# Poti.net
KiCad netlist of a schematic drawn in EAGLE
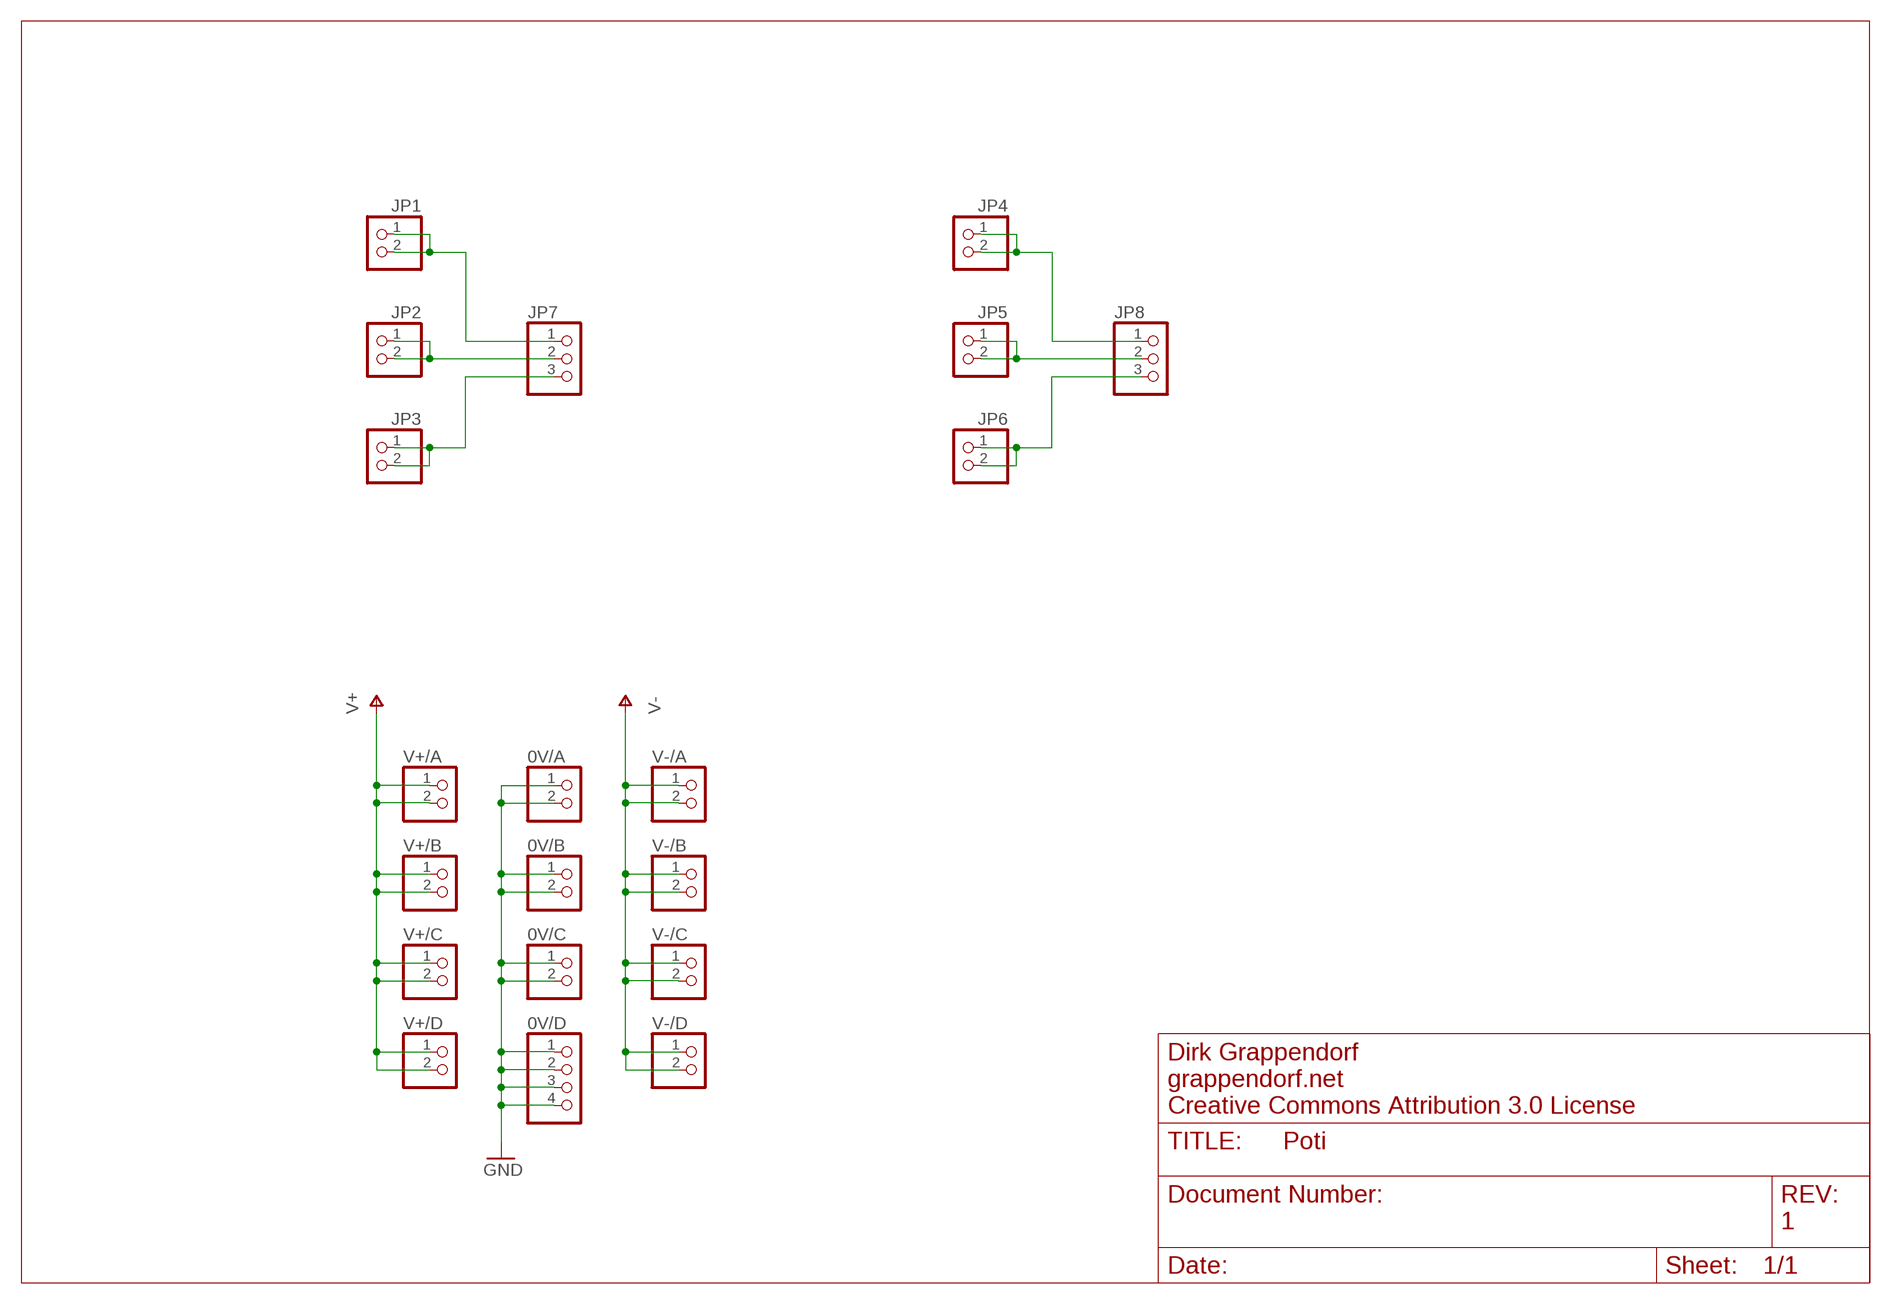
[diagram p0: schematic, sheet 1]

(export (version "E")
  (design (tool "Eeschema 10.0.6"))
  (components
    (comp (ref "0V/A")
      (value "PINHD-1X2")
      (footprint "eagle-import:1X02")
      (libsource (lib "eagle-import") (part "PINHD-1X2"))
    )
    (comp (ref "0V/B")
      (value "PINHD-1X2")
      (footprint "eagle-import:1X02")
      (libsource (lib "eagle-import") (part "PINHD-1X2"))
    )
    (comp (ref "0V/C")
      (value "PINHD-1X2")
      (footprint "eagle-import:1X02")
      (libsource (lib "eagle-import") (part "PINHD-1X2"))
    )
    (comp (ref "0V/D")
      (value "PINHD-1X4")
      (footprint "eagle-import:1X04")
      (libsource (lib "eagle-import") (part "PINHD-1X4"))
    )
    (comp (ref "JP1")
      (value "PINHD-1X2")
      (footprint "eagle-import:1X02")
      (libsource (lib "eagle-import") (part "PINHD-1X2"))
    )
    (comp (ref "JP2")
      (value "PINHD-1X2")
      (footprint "eagle-import:1X02")
      (libsource (lib "eagle-import") (part "PINHD-1X2"))
    )
    (comp (ref "JP3")
      (value "PINHD-1X2")
      (footprint "eagle-import:1X02")
      (libsource (lib "eagle-import") (part "PINHD-1X2"))
    )
    (comp (ref "JP4")
      (value "PINHD-1X2")
      (footprint "eagle-import:1X02")
      (libsource (lib "eagle-import") (part "PINHD-1X2"))
    )
    (comp (ref "JP5")
      (value "PINHD-1X2")
      (footprint "eagle-import:1X02")
      (libsource (lib "eagle-import") (part "PINHD-1X2"))
    )
    (comp (ref "JP6")
      (value "PINHD-1X2")
      (footprint "eagle-import:1X02")
      (libsource (lib "eagle-import") (part "PINHD-1X2"))
    )
    (comp (ref "JP7")
      (value "PINHD-1X3")
      (footprint "eagle-import:1X03")
      (libsource (lib "eagle-import") (part "PINHD-1X3"))
    )
    (comp (ref "JP8")
      (value "PINHD-1X3")
      (footprint "eagle-import:1X03")
      (libsource (lib "eagle-import") (part "PINHD-1X3"))
    )
    (comp (ref "V+/A")
      (value "PINHD-1X2")
      (footprint "eagle-import:1X02")
      (libsource (lib "eagle-import") (part "PINHD-1X2"))
    )
    (comp (ref "V+/B")
      (value "PINHD-1X2")
      (footprint "eagle-import:1X02")
      (libsource (lib "eagle-import") (part "PINHD-1X2"))
    )
    (comp (ref "V+/C")
      (value "PINHD-1X2")
      (footprint "eagle-import:1X02")
      (libsource (lib "eagle-import") (part "PINHD-1X2"))
    )
    (comp (ref "V+/D")
      (value "PINHD-1X2")
      (footprint "eagle-import:1X02")
      (libsource (lib "eagle-import") (part "PINHD-1X2"))
    )
    (comp (ref "V-/A")
      (value "PINHD-1X2")
      (footprint "eagle-import:1X02")
      (libsource (lib "eagle-import") (part "PINHD-1X2"))
    )
    (comp (ref "V-/B")
      (value "PINHD-1X2")
      (footprint "eagle-import:1X02")
      (libsource (lib "eagle-import") (part "PINHD-1X2"))
    )
    (comp (ref "V-/C")
      (value "PINHD-1X2")
      (footprint "eagle-import:1X02")
      (libsource (lib "eagle-import") (part "PINHD-1X2"))
    )
    (comp (ref "V-/D")
      (value "PINHD-1X2")
      (footprint "eagle-import:1X02")
      (libsource (lib "eagle-import") (part "PINHD-1X2"))
    )
  )
  (nets
    (net (code "1") (name "GND") (class "Default")
      (node (ref "0V/A") (pin "1") (pinfunction "1_1") (pintype "passive"))
      (node (ref "0V/A") (pin "2") (pinfunction "2_2") (pintype "passive"))
      (node (ref "0V/B") (pin "1") (pinfunction "1_1") (pintype "passive"))
      (node (ref "0V/B") (pin "2") (pinfunction "2_2") (pintype "passive"))
      (node (ref "0V/C") (pin "1") (pinfunction "1_1") (pintype "passive"))
      (node (ref "0V/C") (pin "2") (pinfunction "2_2") (pintype "passive"))
      (node (ref "0V/D") (pin "1") (pinfunction "1_1") (pintype "passive"))
      (node (ref "0V/D") (pin "2") (pinfunction "2_2") (pintype "passive"))
      (node (ref "0V/D") (pin "3") (pinfunction "3_3") (pintype "passive"))
      (node (ref "0V/D") (pin "4") (pinfunction "4_4") (pintype "passive"))
    )
    (net (code "2") (name "Net-(JP1-Pad1)") (class "Default")
      (node (ref "JP1") (pin "1") (pinfunction "1_1") (pintype "passive"))
      (node (ref "JP1") (pin "2") (pinfunction "2_2") (pintype "passive"))
      (node (ref "JP7") (pin "1") (pinfunction "1_1") (pintype "passive"))
    )
    (net (code "3") (name "Net-(JP2-Pad1)") (class "Default")
      (node (ref "JP2") (pin "1") (pinfunction "1_1") (pintype "passive"))
      (node (ref "JP2") (pin "2") (pinfunction "2_2") (pintype "passive"))
      (node (ref "JP7") (pin "2") (pinfunction "2_2") (pintype "passive"))
    )
    (net (code "4") (name "Net-(JP3-Pad1)") (class "Default")
      (node (ref "JP3") (pin "1") (pinfunction "1_1") (pintype "passive"))
      (node (ref "JP3") (pin "2") (pinfunction "2_2") (pintype "passive"))
      (node (ref "JP7") (pin "3") (pinfunction "3_3") (pintype "passive"))
    )
    (net (code "5") (name "Net-(JP4-Pad1)") (class "Default")
      (node (ref "JP4") (pin "1") (pinfunction "1_1") (pintype "passive"))
      (node (ref "JP4") (pin "2") (pinfunction "2_2") (pintype "passive"))
      (node (ref "JP8") (pin "1") (pinfunction "1_1") (pintype "passive"))
    )
    (net (code "6") (name "Net-(JP5-Pad1)") (class "Default")
      (node (ref "JP5") (pin "1") (pinfunction "1_1") (pintype "passive"))
      (node (ref "JP5") (pin "2") (pinfunction "2_2") (pintype "passive"))
      (node (ref "JP8") (pin "2") (pinfunction "2_2") (pintype "passive"))
    )
    (net (code "7") (name "Net-(JP6-Pad1)") (class "Default")
      (node (ref "JP6") (pin "1") (pinfunction "1_1") (pintype "passive"))
      (node (ref "JP6") (pin "2") (pinfunction "2_2") (pintype "passive"))
      (node (ref "JP8") (pin "3") (pinfunction "3_3") (pintype "passive"))
    )
    (net (code "8") (name "V+") (class "Default")
      (node (ref "V+/A") (pin "1") (pinfunction "1_1") (pintype "passive"))
      (node (ref "V+/A") (pin "2") (pinfunction "2_2") (pintype "passive"))
      (node (ref "V+/B") (pin "1") (pinfunction "1_1") (pintype "passive"))
      (node (ref "V+/B") (pin "2") (pinfunction "2_2") (pintype "passive"))
      (node (ref "V+/C") (pin "1") (pinfunction "1_1") (pintype "passive"))
      (node (ref "V+/C") (pin "2") (pinfunction "2_2") (pintype "passive"))
      (node (ref "V+/D") (pin "1") (pinfunction "1_1") (pintype "passive"))
      (node (ref "V+/D") (pin "2") (pinfunction "2_2") (pintype "passive"))
    )
    (net (code "9") (name "V-") (class "Default")
      (node (ref "V-/A") (pin "1") (pinfunction "1_1") (pintype "passive"))
      (node (ref "V-/A") (pin "2") (pinfunction "2_2") (pintype "passive"))
      (node (ref "V-/B") (pin "1") (pinfunction "1_1") (pintype "passive"))
      (node (ref "V-/B") (pin "2") (pinfunction "2_2") (pintype "passive"))
      (node (ref "V-/C") (pin "1") (pinfunction "1_1") (pintype "passive"))
      (node (ref "V-/C") (pin "2") (pinfunction "2_2") (pintype "passive"))
      (node (ref "V-/D") (pin "1") (pinfunction "1_1") (pintype "passive"))
      (node (ref "V-/D") (pin "2") (pinfunction "2_2") (pintype "passive"))
    )
  )
)
